# TriVCO_board_layout_FINAL_edited_10-22.net
KiCad netlist of a schematic drawn in EAGLE
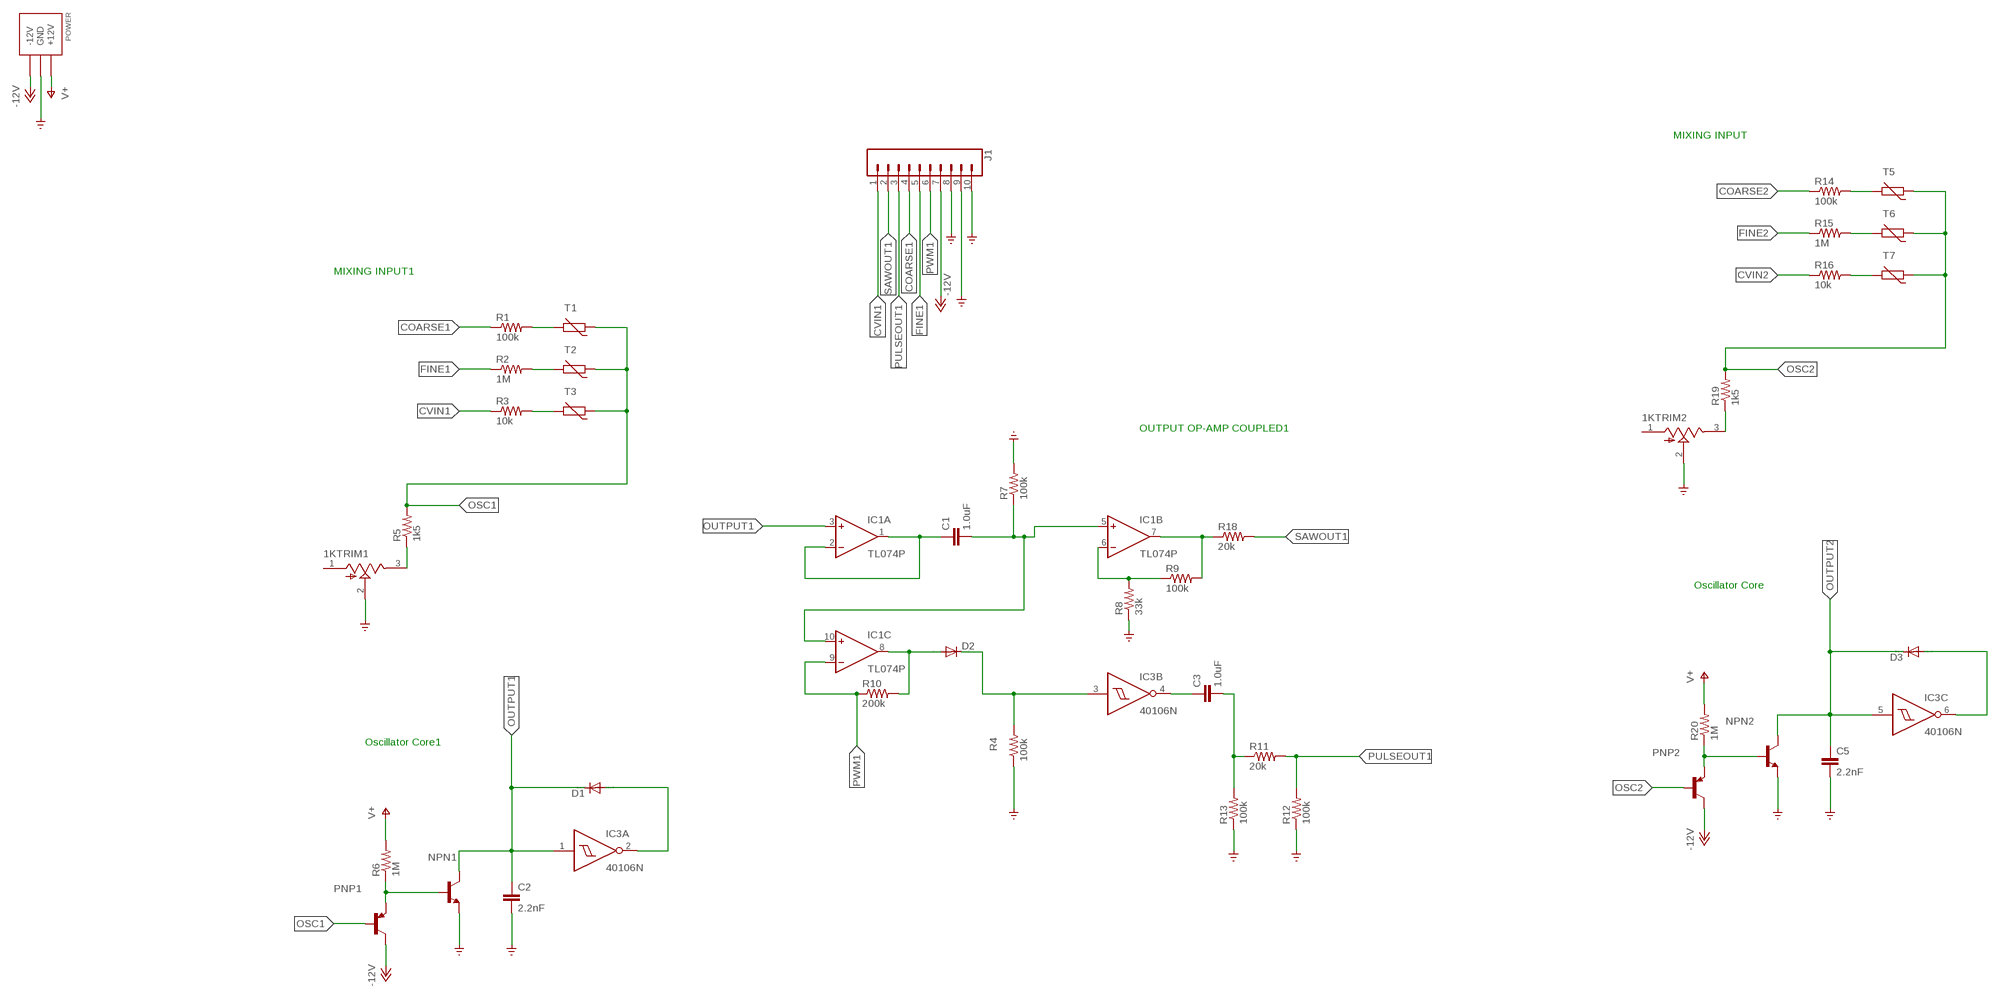
[diagram p0: schematic, sheet 1, part 1 of 2]
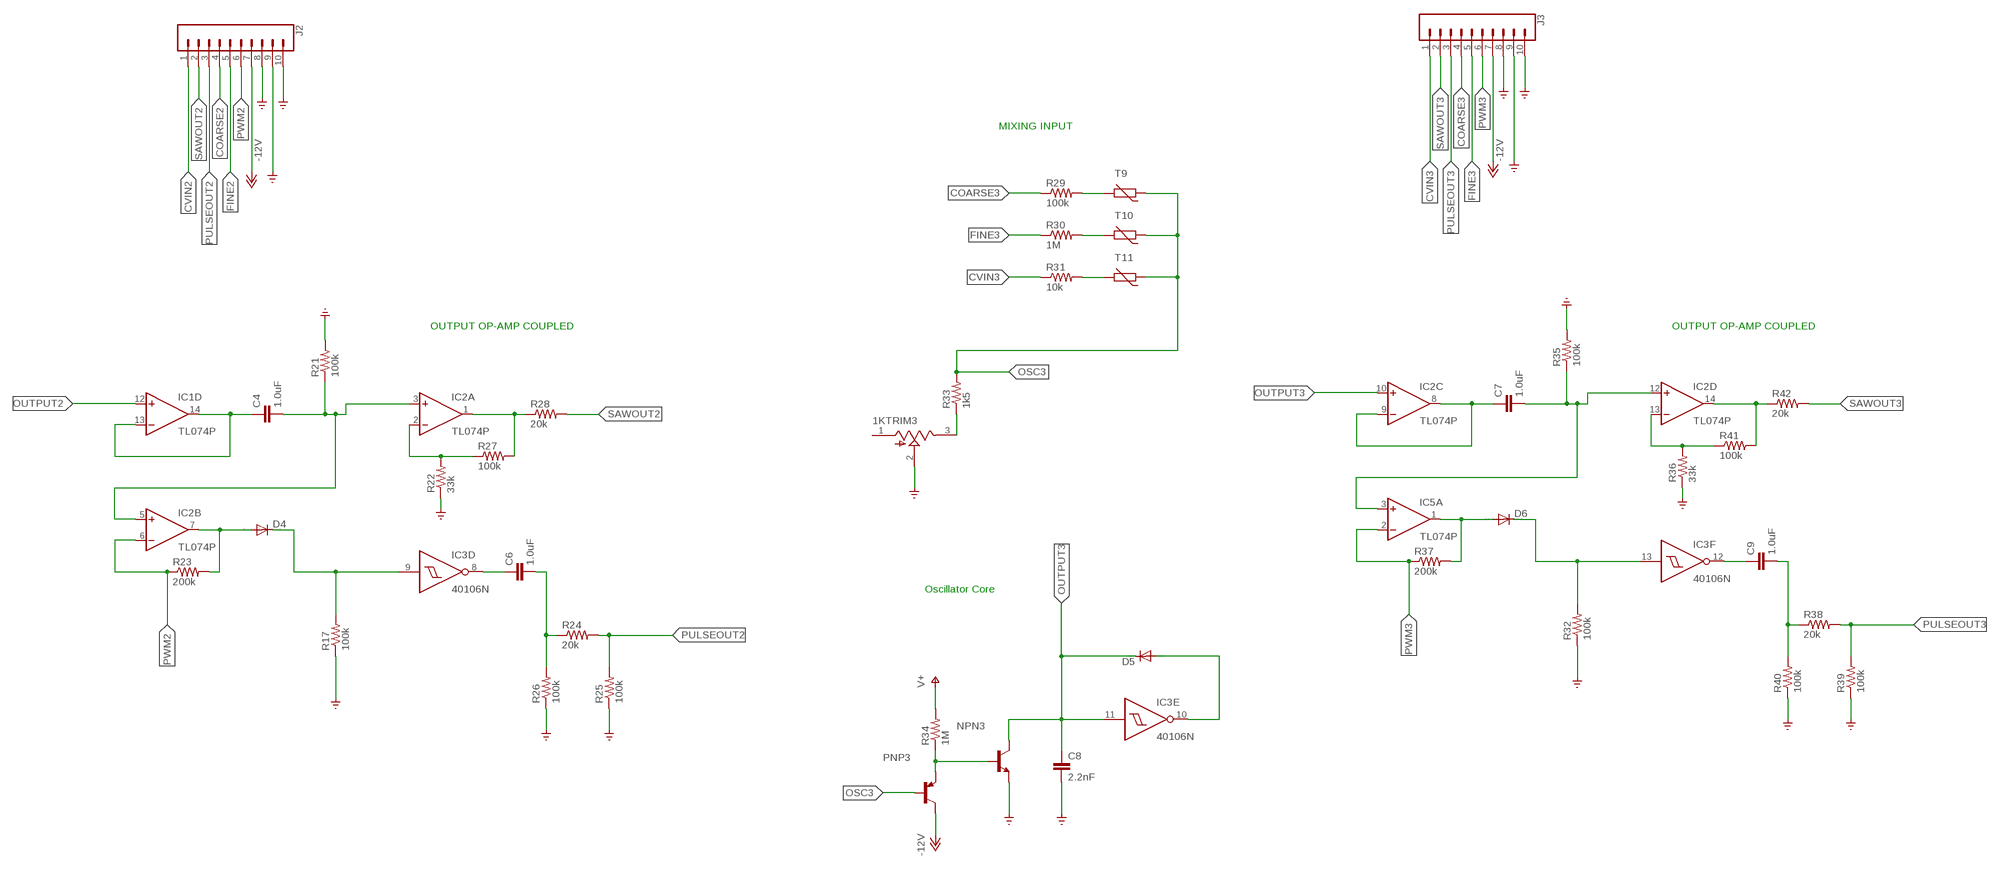
[diagram p1: schematic, sheet 1, part 2 of 2]

(export (version "E")
  (design (tool "Eeschema 10.0.6"))
  (components
    (comp (ref "1KTRIM1")
      (value "3362P-1-102LF")
      (footprint "eagle-import:TRIM_3362P-1-102LF")
      (fields (field (name "MF") "Bourns"))
      (libsource (lib "eagle-import") (part "3362P-1-102LF"))
    )
    (comp (ref "1KTRIM2")
      (value "3362P-1-102LF")
      (footprint "eagle-import:TRIM_3362P-1-102LF")
      (fields (field (name "MF") "Bourns"))
      (libsource (lib "eagle-import") (part "3362P-1-102LF"))
    )
    (comp (ref "1KTRIM3")
      (value "3362P-1-102LF")
      (footprint "eagle-import:TRIM_3362P-1-102LF")
      (fields (field (name "MF") "Bourns"))
      (libsource (lib "eagle-import") (part "3362P-1-102LF"))
    )
    (comp (ref "C1")
      (value "1.0uF")
      (footprint "eagle-import:0603")
      (libsource (lib "eagle-import") (part "1.0UF-0603-16V-10%"))
    )
    (comp (ref "C2")
      (value "2.2nF")
      (footprint "eagle-import:0603")
      (libsource (lib "eagle-import") (part "1.0UF-0603-16V-10%"))
    )
    (comp (ref "C3")
      (value "1.0uF")
      (footprint "eagle-import:0402")
      (libsource (lib "eagle-import") (part "1.0UF-0402-16V-10%"))
    )
    (comp (ref "C4")
      (value "1.0uF")
      (footprint "eagle-import:0603")
      (libsource (lib "eagle-import") (part "1.0UF-0603-16V-10%"))
    )
    (comp (ref "C5")
      (value "2.2nF")
      (footprint "eagle-import:0603")
      (libsource (lib "eagle-import") (part "1.0UF-0603-16V-10%"))
    )
    (comp (ref "C6")
      (value "1.0uF")
      (footprint "eagle-import:0402")
      (libsource (lib "eagle-import") (part "1.0UF-0402-16V-10%"))
    )
    (comp (ref "C7")
      (value "1.0uF")
      (footprint "eagle-import:0603")
      (libsource (lib "eagle-import") (part "1.0UF-0603-16V-10%"))
    )
    (comp (ref "C8")
      (value "2.2nF")
      (footprint "eagle-import:0603")
      (libsource (lib "eagle-import") (part "1.0UF-0603-16V-10%"))
    )
    (comp (ref "C9")
      (value "1.0uF")
      (footprint "eagle-import:0402")
      (libsource (lib "eagle-import") (part "1.0UF-0402-16V-10%"))
    )
    (comp (ref "D1")
      (value "1N4148DO35-7")
      (footprint "eagle-import:DO35-7")
      (libsource (lib "eagle-import") (part "1N4148DO35-7"))
    )
    (comp (ref "D2")
      (value "1N4148DO35-7")
      (footprint "eagle-import:DO35-7")
      (libsource (lib "eagle-import") (part "1N4148DO35-7"))
    )
    (comp (ref "D3")
      (value "1N4148DO35-7")
      (footprint "eagle-import:DO35-7")
      (libsource (lib "eagle-import") (part "1N4148DO35-7"))
    )
    (comp (ref "D4")
      (value "1N4148DO35-7")
      (footprint "eagle-import:DO35-7")
      (libsource (lib "eagle-import") (part "1N4148DO35-7"))
    )
    (comp (ref "D5")
      (value "1N4148DO35-7")
      (footprint "eagle-import:DO35-7")
      (libsource (lib "eagle-import") (part "1N4148DO35-7"))
    )
    (comp (ref "D6")
      (value "1N4148DO35-7")
      (footprint "eagle-import:DO35-7")
      (libsource (lib "eagle-import") (part "1N4148DO35-7"))
    )
    (comp (ref "IC1")
      (value "TL074P")
      (footprint "eagle-import:DIL14")
      (libsource (lib "eagle-import") (part "TL074P"))
    )
    (comp (ref "IC2")
      (value "TL074P")
      (footprint "eagle-import:DIL14")
      (libsource (lib "eagle-import") (part "TL074P"))
    )
    (comp (ref "IC3")
      (value "40106N")
      (footprint "eagle-import:DIL14")
      (libsource (lib "eagle-import") (part "40106N"))
    )
    (comp (ref "IC5")
      (value "TL074P")
      (footprint "eagle-import:DIL14")
      (libsource (lib "eagle-import") (part "TL074P"))
    )
    (comp (ref "J1")
      (value "CONN_10\"")
      (footprint "eagle-import:1X10")
      (libsource (lib "eagle-import") (part "CONN_10{dblquote}"))
    )
    (comp (ref "J2")
      (value "CONN_10\"")
      (footprint "eagle-import:1X10")
      (libsource (lib "eagle-import") (part "CONN_10{dblquote}"))
    )
    (comp (ref "J3")
      (value "CONN_10\"")
      (footprint "eagle-import:1X10")
      (libsource (lib "eagle-import") (part "CONN_10{dblquote}"))
    )
    (comp (ref "NPN1")
      (value "BC485-NPN-TO92-CBE")
      (footprint "eagle-import:TO92-CBE")
      (libsource (lib "eagle-import") (part "-NPN-TO92-CBEBC485"))
    )
    (comp (ref "NPN2")
      (value "BC485-NPN-TO92-CBE")
      (footprint "eagle-import:TO92-CBE")
      (libsource (lib "eagle-import") (part "-NPN-TO92-CBEBC485"))
    )
    (comp (ref "NPN3")
      (value "BC485-NPN-TO92-CBE")
      (footprint "eagle-import:TO92-CBE")
      (libsource (lib "eagle-import") (part "-NPN-TO92-CBEBC485"))
    )
    (comp (ref "PNP1")
      (value "BC450-PNP-TO92-EBC")
      (footprint "eagle-import:TO92-EBC")
      (libsource (lib "eagle-import") (part "-PNP-TO92-EBCBC450"))
    )
    (comp (ref "PNP2")
      (value "BC450-PNP-TO92-EBC")
      (footprint "eagle-import:TO92-EBC")
      (libsource (lib "eagle-import") (part "-PNP-TO92-EBCBC450"))
    )
    (comp (ref "PNP3")
      (value "BC450-PNP-TO92-EBC")
      (footprint "eagle-import:TO92-EBC")
      (libsource (lib "eagle-import") (part "-PNP-TO92-EBCBC450"))
    )
    (comp (ref "POWER")
      (value "POWER_SIMPLE10")
      (footprint "eagle-import:POWER_10")
      (libsource (lib "eagle-import") (part "POWER_SIMPLE10"))
    )
    (comp (ref "R1")
      (value "100k")
      (footprint "eagle-import:0207_10")
      (libsource (lib "eagle-import") (part "R-US_0207/10"))
    )
    (comp (ref "R2")
      (value "1M")
      (footprint "eagle-import:0207_10")
      (libsource (lib "eagle-import") (part "R-US_0207/10"))
    )
    (comp (ref "R3")
      (value "10k")
      (footprint "eagle-import:0207_10")
      (libsource (lib "eagle-import") (part "R-US_0207/10"))
    )
    (comp (ref "R4")
      (value "100k")
      (footprint "eagle-import:0207_10")
      (libsource (lib "eagle-import") (part "R-US_0207/10"))
    )
    (comp (ref "R5")
      (value "1k5")
      (footprint "eagle-import:0207_10")
      (libsource (lib "eagle-import") (part "R-US_0207/10"))
    )
    (comp (ref "R6")
      (value "1M")
      (footprint "eagle-import:0207_10")
      (libsource (lib "eagle-import") (part "R-US_0207/10"))
    )
    (comp (ref "R7")
      (value "100k")
      (footprint "eagle-import:0207_10")
      (libsource (lib "eagle-import") (part "R-US_0207/10"))
    )
    (comp (ref "R8")
      (value "33k")
      (footprint "eagle-import:0207_10")
      (libsource (lib "eagle-import") (part "R-US_0207/10"))
    )
    (comp (ref "R9")
      (value "100k")
      (footprint "eagle-import:0207_10")
      (libsource (lib "eagle-import") (part "R-US_0207/10"))
    )
    (comp (ref "R10")
      (value "200k")
      (footprint "eagle-import:0207_10")
      (libsource (lib "eagle-import") (part "R-US_0207/10"))
    )
    (comp (ref "R11")
      (value "20k")
      (footprint "eagle-import:0207_10")
      (libsource (lib "eagle-import") (part "R-US_0207/10"))
    )
    (comp (ref "R12")
      (value "100k")
      (footprint "eagle-import:0207_10")
      (libsource (lib "eagle-import") (part "R-US_0207/10"))
    )
    (comp (ref "R13")
      (value "100k")
      (footprint "eagle-import:0207_10")
      (libsource (lib "eagle-import") (part "R-US_0207/10"))
    )
    (comp (ref "R14")
      (value "100k")
      (footprint "eagle-import:0207_10")
      (libsource (lib "eagle-import") (part "R-US_0207/10"))
    )
    (comp (ref "R15")
      (value "1M")
      (footprint "eagle-import:0207_10")
      (libsource (lib "eagle-import") (part "R-US_0207/10"))
    )
    (comp (ref "R16")
      (value "10k")
      (footprint "eagle-import:0207_10")
      (libsource (lib "eagle-import") (part "R-US_0207/10"))
    )
    (comp (ref "R17")
      (value "100k")
      (footprint "eagle-import:0207_10")
      (libsource (lib "eagle-import") (part "R-US_0207/10"))
    )
    (comp (ref "R18")
      (value "20k")
      (footprint "eagle-import:0207_10")
      (libsource (lib "eagle-import") (part "R-US_0207/10"))
    )
    (comp (ref "R19")
      (value "1k5")
      (footprint "eagle-import:0207_10")
      (libsource (lib "eagle-import") (part "R-US_0207/10"))
    )
    (comp (ref "R20")
      (value "1M")
      (footprint "eagle-import:0207_10")
      (libsource (lib "eagle-import") (part "R-US_0207/10"))
    )
    (comp (ref "R21")
      (value "100k")
      (footprint "eagle-import:0207_10")
      (libsource (lib "eagle-import") (part "R-US_0207/10"))
    )
    (comp (ref "R22")
      (value "33k")
      (footprint "eagle-import:0207_10")
      (libsource (lib "eagle-import") (part "R-US_0207/10"))
    )
    (comp (ref "R23")
      (value "200k")
      (footprint "eagle-import:0207_10")
      (libsource (lib "eagle-import") (part "R-US_0207/10"))
    )
    (comp (ref "R24")
      (value "20k")
      (footprint "eagle-import:0207_10")
      (libsource (lib "eagle-import") (part "R-US_0207/10"))
    )
    (comp (ref "R25")
      (value "100k")
      (footprint "eagle-import:0207_10")
      (libsource (lib "eagle-import") (part "R-US_0207/10"))
    )
    (comp (ref "R26")
      (value "100k")
      (footprint "eagle-import:0207_10")
      (libsource (lib "eagle-import") (part "R-US_0207/10"))
    )
    (comp (ref "R27")
      (value "100k")
      (footprint "eagle-import:0207_10")
      (libsource (lib "eagle-import") (part "R-US_0207/10"))
    )
    (comp (ref "R28")
      (value "20k")
      (footprint "eagle-import:0207_10")
      (libsource (lib "eagle-import") (part "R-US_0207/10"))
    )
    (comp (ref "R29")
      (value "100k")
      (footprint "eagle-import:0207_10")
      (libsource (lib "eagle-import") (part "R-US_0207/10"))
    )
    (comp (ref "R30")
      (value "1M")
      (footprint "eagle-import:0207_10")
      (libsource (lib "eagle-import") (part "R-US_0207/10"))
    )
    (comp (ref "R31")
      (value "10k")
      (footprint "eagle-import:0207_10")
      (libsource (lib "eagle-import") (part "R-US_0207/10"))
    )
    (comp (ref "R32")
      (value "100k")
      (footprint "eagle-import:0207_10")
      (libsource (lib "eagle-import") (part "R-US_0207/10"))
    )
    (comp (ref "R33")
      (value "1k5")
      (footprint "eagle-import:0207_10")
      (libsource (lib "eagle-import") (part "R-US_0207/10"))
    )
    (comp (ref "R34")
      (value "1M")
      (footprint "eagle-import:0207_10")
      (libsource (lib "eagle-import") (part "R-US_0207/10"))
    )
    (comp (ref "R35")
      (value "100k")
      (footprint "eagle-import:0207_10")
      (libsource (lib "eagle-import") (part "R-US_0207/10"))
    )
    (comp (ref "R36")
      (value "33k")
      (footprint "eagle-import:0207_10")
      (libsource (lib "eagle-import") (part "R-US_0207/10"))
    )
    (comp (ref "R37")
      (value "200k")
      (footprint "eagle-import:0207_10")
      (libsource (lib "eagle-import") (part "R-US_0207/10"))
    )
    (comp (ref "R38")
      (value "20k")
      (footprint "eagle-import:0207_10")
      (libsource (lib "eagle-import") (part "R-US_0207/10"))
    )
    (comp (ref "R39")
      (value "100k")
      (footprint "eagle-import:0207_10")
      (libsource (lib "eagle-import") (part "R-US_0207/10"))
    )
    (comp (ref "R40")
      (value "100k")
      (footprint "eagle-import:0207_10")
      (libsource (lib "eagle-import") (part "R-US_0207/10"))
    )
    (comp (ref "R41")
      (value "100k")
      (footprint "eagle-import:0207_10")
      (libsource (lib "eagle-import") (part "R-US_0207/10"))
    )
    (comp (ref "R42")
      (value "20k")
      (footprint "eagle-import:0207_10")
      (libsource (lib "eagle-import") (part "R-US_0207/10"))
    )
    (comp (ref "T1")
      (value "THERMISTOR-5")
      (footprint "eagle-import:R-5")
      (libsource (lib "eagle-import") (part "THERMISTOR-5"))
    )
    (comp (ref "T2")
      (value "THERMISTOR-5")
      (footprint "eagle-import:R-5")
      (libsource (lib "eagle-import") (part "THERMISTOR-5"))
    )
    (comp (ref "T3")
      (value "THERMISTOR-5")
      (footprint "eagle-import:R-5")
      (libsource (lib "eagle-import") (part "THERMISTOR-5"))
    )
    (comp (ref "T5")
      (value "THERMISTOR-5")
      (footprint "eagle-import:R-5")
      (libsource (lib "eagle-import") (part "THERMISTOR-5"))
    )
    (comp (ref "T6")
      (value "THERMISTOR-5")
      (footprint "eagle-import:R-5")
      (libsource (lib "eagle-import") (part "THERMISTOR-5"))
    )
    (comp (ref "T7")
      (value "THERMISTOR-5")
      (footprint "eagle-import:R-5")
      (libsource (lib "eagle-import") (part "THERMISTOR-5"))
    )
    (comp (ref "T9")
      (value "THERMISTOR-5")
      (footprint "eagle-import:R-5")
      (libsource (lib "eagle-import") (part "THERMISTOR-5"))
    )
    (comp (ref "T10")
      (value "THERMISTOR-5")
      (footprint "eagle-import:R-5")
      (libsource (lib "eagle-import") (part "THERMISTOR-5"))
    )
    (comp (ref "T11")
      (value "THERMISTOR-5")
      (footprint "eagle-import:R-5")
      (libsource (lib "eagle-import") (part "THERMISTOR-5"))
    )
  )
  (nets
    (net (code "1") (name "-12V") (class "Default")
      (node (ref "J1") (pin "7") (pinfunction "7_7") (pintype "passive"))
      (node (ref "J2") (pin "7") (pinfunction "7_7") (pintype "passive"))
      (node (ref "J3") (pin "7") (pinfunction "7_7") (pintype "passive"))
      (node (ref "PNP1") (pin "C") (pinfunction "C_C") (pintype "passive"))
      (node (ref "PNP2") (pin "C") (pinfunction "C_C") (pintype "passive"))
      (node (ref "PNP3") (pin "C") (pinfunction "C_C") (pintype "passive"))
      (node (ref "POWER") (pin "1") (pinfunction "-12V_1") (pintype "bidirectional"))
      (node (ref "POWER") (pin "2") (pinfunction "-12V_2") (pintype "bidirectional"))
    )
    (net (code "2") (name "COARSE1") (class "Default")
      (node (ref "J1") (pin "4") (pinfunction "4_4") (pintype "passive"))
      (node (ref "R1") (pin "1") (pinfunction "1_1") (pintype "passive"))
    )
    (net (code "3") (name "COARSE2") (class "Default")
      (node (ref "J2") (pin "4") (pinfunction "4_4") (pintype "passive"))
      (node (ref "R14") (pin "1") (pinfunction "1_1") (pintype "passive"))
    )
    (net (code "4") (name "COARSE3") (class "Default")
      (node (ref "J3") (pin "4") (pinfunction "4_4") (pintype "passive"))
      (node (ref "R29") (pin "1") (pinfunction "1_1") (pintype "passive"))
    )
    (net (code "5") (name "CVIN1") (class "Default")
      (node (ref "J1") (pin "1") (pinfunction "1_1") (pintype "passive"))
      (node (ref "R3") (pin "1") (pinfunction "1_1") (pintype "passive"))
    )
    (net (code "6") (name "CVIN2") (class "Default")
      (node (ref "J2") (pin "1") (pinfunction "1_1") (pintype "passive"))
      (node (ref "R16") (pin "1") (pinfunction "1_1") (pintype "passive"))
    )
    (net (code "7") (name "CVIN3") (class "Default")
      (node (ref "J3") (pin "1") (pinfunction "1_1") (pintype "passive"))
      (node (ref "R31") (pin "1") (pinfunction "1_1") (pintype "passive"))
    )
    (net (code "8") (name "FINE1") (class "Default")
      (node (ref "J1") (pin "5") (pinfunction "5_5") (pintype "passive"))
      (node (ref "R2") (pin "1") (pinfunction "1_1") (pintype "passive"))
    )
    (net (code "9") (name "FINE2") (class "Default")
      (node (ref "J2") (pin "5") (pinfunction "5_5") (pintype "passive"))
      (node (ref "R15") (pin "1") (pinfunction "1_1") (pintype "passive"))
    )
    (net (code "10") (name "FINE3") (class "Default")
      (node (ref "J3") (pin "5") (pinfunction "5_5") (pintype "passive"))
      (node (ref "R30") (pin "1") (pinfunction "1_1") (pintype "passive"))
    )
    (net (code "11") (name "Net-(1KTRIM1-CW)") (class "Default")
      (node (ref "1KTRIM1") (pin "3") (pinfunction "CW_3") (pintype "passive"))
      (node (ref "R5") (pin "1") (pinfunction "1_1") (pintype "passive"))
    )
    (net (code "12") (name "Net-(1KTRIM2-CW)") (class "Default")
      (node (ref "1KTRIM2") (pin "3") (pinfunction "CW_3") (pintype "passive"))
      (node (ref "R19") (pin "1") (pinfunction "1_1") (pintype "passive"))
    )
    (net (code "13") (name "Net-(1KTRIM3-CW)") (class "Default")
      (node (ref "1KTRIM3") (pin "3") (pinfunction "CW_3") (pintype "passive"))
      (node (ref "R33") (pin "1") (pinfunction "1_1") (pintype "passive"))
    )
    (net (code "14") (name "Net-(C3-Pad2)") (class "Default")
      (node (ref "C3") (pin "2") (pinfunction "2_2") (pintype "passive"))
      (node (ref "R11") (pin "1") (pinfunction "1_1") (pintype "passive"))
      (node (ref "R13") (pin "2") (pinfunction "2_2") (pintype "passive"))
    )
    (net (code "15") (name "Net-(C6-Pad2)") (class "Default")
      (node (ref "C6") (pin "2") (pinfunction "2_2") (pintype "passive"))
      (node (ref "R24") (pin "1") (pinfunction "1_1") (pintype "passive"))
      (node (ref "R26") (pin "2") (pinfunction "2_2") (pintype "passive"))
    )
    (net (code "16") (name "Net-(C9-Pad2)") (class "Default")
      (node (ref "C9") (pin "2") (pinfunction "2_2") (pintype "passive"))
      (node (ref "R38") (pin "1") (pinfunction "1_1") (pintype "passive"))
      (node (ref "R40") (pin "2") (pinfunction "2_2") (pintype "passive"))
    )
    (net (code "17") (name "Net-(IC1A--IN)") (class "Default")
      (node (ref "C1") (pin "1") (pinfunction "1_1") (pintype "passive"))
      (node (ref "IC1") (pin "1") (pinfunction "OUT_1") (pintype "output"))
      (node (ref "IC1") (pin "2") (pinfunction "-IN_2") (pintype "input"))
    )
    (net (code "18") (name "Net-(IC1B-+IN)") (class "Default")
      (node (ref "C1") (pin "2") (pinfunction "2_2") (pintype "passive"))
      (node (ref "IC1") (pin "10") (pinfunction "+IN_10") (pintype "input"))
      (node (ref "IC1") (pin "5") (pinfunction "+IN_5") (pintype "input"))
      (node (ref "R7") (pin "1") (pinfunction "1_1") (pintype "passive"))
    )
    (net (code "19") (name "Net-(IC1B--IN)") (class "Default")
      (node (ref "IC1") (pin "6") (pinfunction "-IN_6") (pintype "input"))
      (node (ref "R8") (pin "2") (pinfunction "2_2") (pintype "passive"))
      (node (ref "R9") (pin "1") (pinfunction "1_1") (pintype "passive"))
    )
    (net (code "20") (name "Net-(IC1B-OUT)") (class "Default")
      (node (ref "IC1") (pin "7") (pinfunction "OUT_7") (pintype "output"))
      (node (ref "R18") (pin "1") (pinfunction "1_1") (pintype "passive"))
      (node (ref "R9") (pin "2") (pinfunction "2_2") (pintype "passive"))
    )
    (net (code "21") (name "Net-(IC1C-OUT)") (class "Default")
      (node (ref "D2") (pin "A") (pinfunction "A_A") (pintype "passive"))
      (node (ref "IC1") (pin "8") (pinfunction "OUT_8") (pintype "output"))
      (node (ref "R10") (pin "2") (pinfunction "2_2") (pintype "passive"))
    )
    (net (code "22") (name "Net-(IC1D--IN)") (class "Default")
      (node (ref "C4") (pin "1") (pinfunction "1_1") (pintype "passive"))
      (node (ref "IC1") (pin "13") (pinfunction "-IN_13") (pintype "input"))
      (node (ref "IC1") (pin "14") (pinfunction "OUT_14") (pintype "output"))
    )
    (net (code "23") (name "Net-(IC2A-+IN)") (class "Default")
      (node (ref "C4") (pin "2") (pinfunction "2_2") (pintype "passive"))
      (node (ref "IC2") (pin "3") (pinfunction "+IN_3") (pintype "input"))
      (node (ref "IC2") (pin "5") (pinfunction "+IN_5") (pintype "input"))
      (node (ref "R21") (pin "1") (pinfunction "1_1") (pintype "passive"))
    )
    (net (code "24") (name "Net-(IC2A--IN)") (class "Default")
      (node (ref "IC2") (pin "2") (pinfunction "-IN_2") (pintype "input"))
      (node (ref "R22") (pin "2") (pinfunction "2_2") (pintype "passive"))
      (node (ref "R27") (pin "1") (pinfunction "1_1") (pintype "passive"))
    )
    (net (code "25") (name "Net-(IC2A-OUT)") (class "Default")
      (node (ref "IC2") (pin "1") (pinfunction "OUT_1") (pintype "output"))
      (node (ref "R27") (pin "2") (pinfunction "2_2") (pintype "passive"))
      (node (ref "R28") (pin "1") (pinfunction "1_1") (pintype "passive"))
    )
    (net (code "26") (name "Net-(IC2B-OUT)") (class "Default")
      (node (ref "D4") (pin "A") (pinfunction "A_A") (pintype "passive"))
      (node (ref "IC2") (pin "7") (pinfunction "OUT_7") (pintype "output"))
      (node (ref "R23") (pin "2") (pinfunction "2_2") (pintype "passive"))
    )
    (net (code "27") (name "Net-(IC2C--IN)") (class "Default")
      (node (ref "C7") (pin "1") (pinfunction "1_1") (pintype "passive"))
      (node (ref "IC2") (pin "8") (pinfunction "OUT_8") (pintype "output"))
      (node (ref "IC2") (pin "9") (pinfunction "-IN_9") (pintype "input"))
    )
    (net (code "28") (name "Net-(IC2D-+IN)") (class "Default")
      (node (ref "C7") (pin "2") (pinfunction "2_2") (pintype "passive"))
      (node (ref "IC2") (pin "12") (pinfunction "+IN_12") (pintype "input"))
      (node (ref "IC5") (pin "3") (pinfunction "+IN_3") (pintype "input"))
      (node (ref "R35") (pin "1") (pinfunction "1_1") (pintype "passive"))
    )
    (net (code "29") (name "Net-(IC2D--IN)") (class "Default")
      (node (ref "IC2") (pin "13") (pinfunction "-IN_13") (pintype "input"))
      (node (ref "R36") (pin "2") (pinfunction "2_2") (pintype "passive"))
      (node (ref "R41") (pin "1") (pinfunction "1_1") (pintype "passive"))
    )
    (net (code "30") (name "Net-(IC2D-OUT)") (class "Default")
      (node (ref "IC2") (pin "14") (pinfunction "OUT_14") (pintype "output"))
      (node (ref "R41") (pin "2") (pinfunction "2_2") (pintype "passive"))
      (node (ref "R42") (pin "1") (pinfunction "1_1") (pintype "passive"))
    )
    (net (code "31") (name "Net-(IC3A-O)") (class "Default")
      (node (ref "D1") (pin "A") (pinfunction "A_A") (pintype "passive"))
      (node (ref "IC3") (pin "2") (pinfunction "O_2") (pintype "output"))
    )
    (net (code "32") (name "Net-(IC3B-I)") (class "Default")
      (node (ref "D2") (pin "C") (pinfunction "C_C") (pintype "passive"))
      (node (ref "IC3") (pin "3") (pinfunction "I_3") (pintype "input"))
      (node (ref "R4") (pin "2") (pinfunction "2_2") (pintype "passive"))
    )
    (net (code "33") (name "Net-(IC3B-O)") (class "Default")
      (node (ref "C3") (pin "1") (pinfunction "1_1") (pintype "passive"))
      (node (ref "IC3") (pin "4") (pinfunction "O_4") (pintype "output"))
    )
    (net (code "34") (name "Net-(IC3C-O)") (class "Default")
      (node (ref "D3") (pin "A") (pinfunction "A_A") (pintype "passive"))
      (node (ref "IC3") (pin "6") (pinfunction "O_6") (pintype "output"))
    )
    (net (code "35") (name "Net-(IC3D-I)") (class "Default")
      (node (ref "D4") (pin "C") (pinfunction "C_C") (pintype "passive"))
      (node (ref "IC3") (pin "9") (pinfunction "I_9") (pintype "input"))
      (node (ref "R17") (pin "2") (pinfunction "2_2") (pintype "passive"))
    )
    (net (code "36") (name "Net-(IC3D-O)") (class "Default")
      (node (ref "C6") (pin "1") (pinfunction "1_1") (pintype "passive"))
      (node (ref "IC3") (pin "8") (pinfunction "O_8") (pintype "output"))
    )
    (net (code "37") (name "Net-(IC3E-O)") (class "Default")
      (node (ref "D5") (pin "A") (pinfunction "A_A") (pintype "passive"))
      (node (ref "IC3") (pin "10") (pinfunction "O_10") (pintype "output"))
    )
    (net (code "38") (name "Net-(IC3F-I)") (class "Default")
      (node (ref "D6") (pin "C") (pinfunction "C_C") (pintype "passive"))
      (node (ref "IC3") (pin "13") (pinfunction "I_13") (pintype "input"))
      (node (ref "R32") (pin "2") (pinfunction "2_2") (pintype "passive"))
    )
    (net (code "39") (name "Net-(IC3F-O)") (class "Default")
      (node (ref "C9") (pin "1") (pinfunction "1_1") (pintype "passive"))
      (node (ref "IC3") (pin "12") (pinfunction "O_12") (pintype "output"))
    )
    (net (code "40") (name "Net-(IC5A-OUT)") (class "Default")
      (node (ref "D6") (pin "A") (pinfunction "A_A") (pintype "passive"))
      (node (ref "IC5") (pin "1") (pinfunction "OUT_1") (pintype "output"))
      (node (ref "R37") (pin "2") (pinfunction "2_2") (pintype "passive"))
    )
    (net (code "41") (name "Net-(NPN1-PadB)") (class "Default")
      (node (ref "NPN1") (pin "B") (pinfunction "B_B") (pintype "passive"))
      (node (ref "PNP1") (pin "E") (pinfunction "E_E") (pintype "passive"))
      (node (ref "R6") (pin "1") (pinfunction "1_1") (pintype "passive"))
    )
    (net (code "42") (name "Net-(NPN2-PadB)") (class "Default")
      (node (ref "NPN2") (pin "B") (pinfunction "B_B") (pintype "passive"))
      (node (ref "PNP2") (pin "E") (pinfunction "E_E") (pintype "passive"))
      (node (ref "R20") (pin "1") (pinfunction "1_1") (pintype "passive"))
    )
    (net (code "43") (name "Net-(NPN3-PadB)") (class "Default")
      (node (ref "NPN3") (pin "B") (pinfunction "B_B") (pintype "passive"))
      (node (ref "PNP3") (pin "E") (pinfunction "E_E") (pintype "passive"))
      (node (ref "R34") (pin "1") (pinfunction "1_1") (pintype "passive"))
    )
    (net (code "44") (name "Net-(R1-Pad2)") (class "Default")
      (node (ref "R1") (pin "2") (pinfunction "2_2") (pintype "passive"))
      (node (ref "T1") (pin "2") (pinfunction "2_2") (pintype "passive"))
    )
    (net (code "45") (name "Net-(R2-Pad2)") (class "Default")
      (node (ref "R2") (pin "2") (pinfunction "2_2") (pintype "passive"))
      (node (ref "T2") (pin "2") (pinfunction "2_2") (pintype "passive"))
    )
    (net (code "46") (name "Net-(R3-Pad2)") (class "Default")
      (node (ref "R3") (pin "2") (pinfunction "2_2") (pintype "passive"))
      (node (ref "T3") (pin "2") (pinfunction "2_2") (pintype "passive"))
    )
    (net (code "47") (name "Net-(R14-Pad2)") (class "Default")
      (node (ref "R14") (pin "2") (pinfunction "2_2") (pintype "passive"))
      (node (ref "T5") (pin "2") (pinfunction "2_2") (pintype "passive"))
    )
    (net (code "48") (name "Net-(R15-Pad2)") (class "Default")
      (node (ref "R15") (pin "2") (pinfunction "2_2") (pintype "passive"))
      (node (ref "T6") (pin "2") (pinfunction "2_2") (pintype "passive"))
    )
    (net (code "49") (name "Net-(R16-Pad2)") (class "Default")
      (node (ref "R16") (pin "2") (pinfunction "2_2") (pintype "passive"))
      (node (ref "T7") (pin "2") (pinfunction "2_2") (pintype "passive"))
    )
    (net (code "50") (name "Net-(R29-Pad2)") (class "Default")
      (node (ref "R29") (pin "2") (pinfunction "2_2") (pintype "passive"))
      (node (ref "T9") (pin "2") (pinfunction "2_2") (pintype "passive"))
    )
    (net (code "51") (name "Net-(R30-Pad2)") (class "Default")
      (node (ref "R30") (pin "2") (pinfunction "2_2") (pintype "passive"))
      (node (ref "T10") (pin "2") (pinfunction "2_2") (pintype "passive"))
    )
    (net (code "52") (name "Net-(R31-Pad2)") (class "Default")
      (node (ref "R31") (pin "2") (pinfunction "2_2") (pintype "passive"))
      (node (ref "T11") (pin "2") (pinfunction "2_2") (pintype "passive"))
    )
    (net (code "53") (name "OSC1") (class "Default")
      (node (ref "PNP1") (pin "B") (pinfunction "B_B") (pintype "passive"))
      (node (ref "R5") (pin "2") (pinfunction "2_2") (pintype "passive"))
      (node (ref "T1") (pin "1") (pinfunction "1_1") (pintype "passive"))
      (node (ref "T2") (pin "1") (pinfunction "1_1") (pintype "passive"))
      (node (ref "T3") (pin "1") (pinfunction "1_1") (pintype "passive"))
    )
    (net (code "54") (name "OSC2") (class "Default")
      (node (ref "PNP2") (pin "B") (pinfunction "B_B") (pintype "passive"))
      (node (ref "R19") (pin "2") (pinfunction "2_2") (pintype "passive"))
      (node (ref "T5") (pin "1") (pinfunction "1_1") (pintype "passive"))
      (node (ref "T6") (pin "1") (pinfunction "1_1") (pintype "passive"))
      (node (ref "T7") (pin "1") (pinfunction "1_1") (pintype "passive"))
    )
    (net (code "55") (name "OSC3") (class "Default")
      (node (ref "PNP3") (pin "B") (pinfunction "B_B") (pintype "passive"))
      (node (ref "R33") (pin "2") (pinfunction "2_2") (pintype "passive"))
      (node (ref "T10") (pin "1") (pinfunction "1_1") (pintype "passive"))
      (node (ref "T11") (pin "1") (pinfunction "1_1") (pintype "passive"))
      (node (ref "T9") (pin "1") (pinfunction "1_1") (pintype "passive"))
    )
    (net (code "56") (name "OUTPUT1") (class "Default")
      (node (ref "C2") (pin "1") (pinfunction "1_1") (pintype "passive"))
      (node (ref "D1") (pin "C") (pinfunction "C_C") (pintype "passive"))
      (node (ref "IC1") (pin "3") (pinfunction "+IN_3") (pintype "input"))
      (node (ref "IC3") (pin "1") (pinfunction "I_1") (pintype "input"))
      (node (ref "NPN1") (pin "C") (pinfunction "C_C") (pintype "passive"))
    )
    (net (code "57") (name "OUTPUT2") (class "Default")
      (node (ref "C5") (pin "1") (pinfunction "1_1") (pintype "passive"))
      (node (ref "D3") (pin "C") (pinfunction "C_C") (pintype "passive"))
      (node (ref "IC1") (pin "12") (pinfunction "+IN_12") (pintype "input"))
      (node (ref "IC3") (pin "5") (pinfunction "I_5") (pintype "input"))
      (node (ref "NPN2") (pin "C") (pinfunction "C_C") (pintype "passive"))
    )
    (net (code "58") (name "OUTPUT3") (class "Default")
      (node (ref "C8") (pin "1") (pinfunction "1_1") (pintype "passive"))
      (node (ref "D5") (pin "C") (pinfunction "C_C") (pintype "passive"))
      (node (ref "IC2") (pin "10") (pinfunction "+IN_10") (pintype "input"))
      (node (ref "IC3") (pin "11") (pinfunction "I_11") (pintype "input"))
      (node (ref "NPN3") (pin "C") (pinfunction "C_C") (pintype "passive"))
    )
    (net (code "59") (name "PULSEOUT1") (class "Default")
      (node (ref "J1") (pin "3") (pinfunction "3_3") (pintype "passive"))
      (node (ref "R11") (pin "2") (pinfunction "2_2") (pintype "passive"))
      (node (ref "R12") (pin "2") (pinfunction "2_2") (pintype "passive"))
    )
    (net (code "60") (name "PULSEOUT2") (class "Default")
      (node (ref "J2") (pin "3") (pinfunction "3_3") (pintype "passive"))
      (node (ref "R24") (pin "2") (pinfunction "2_2") (pintype "passive"))
      (node (ref "R25") (pin "2") (pinfunction "2_2") (pintype "passive"))
    )
    (net (code "61") (name "PULSEOUT3") (class "Default")
      (node (ref "J3") (pin "3") (pinfunction "3_3") (pintype "passive"))
      (node (ref "R38") (pin "2") (pinfunction "2_2") (pintype "passive"))
      (node (ref "R39") (pin "2") (pinfunction "2_2") (pintype "passive"))
    )
    (net (code "62") (name "PWM1") (class "Default")
      (node (ref "IC1") (pin "9") (pinfunction "-IN_9") (pintype "input"))
      (node (ref "J1") (pin "6") (pinfunction "6_6") (pintype "passive"))
      (node (ref "R10") (pin "1") (pinfunction "1_1") (pintype "passive"))
    )
    (net (code "63") (name "PWM2") (class "Default")
      (node (ref "IC2") (pin "6") (pinfunction "-IN_6") (pintype "input"))
      (node (ref "J2") (pin "6") (pinfunction "6_6") (pintype "passive"))
      (node (ref "R23") (pin "1") (pinfunction "1_1") (pintype "passive"))
    )
    (net (code "64") (name "PWM3") (class "Default")
      (node (ref "IC5") (pin "2") (pinfunction "-IN_2") (pintype "input"))
      (node (ref "J3") (pin "6") (pinfunction "6_6") (pintype "passive"))
      (node (ref "R37") (pin "1") (pinfunction "1_1") (pintype "passive"))
    )
    (net (code "65") (name "SAWOUT1") (class "Default")
      (node (ref "J1") (pin "2") (pinfunction "2_2") (pintype "passive"))
      (node (ref "R18") (pin "2") (pinfunction "2_2") (pintype "passive"))
    )
    (net (code "66") (name "SAWOUT2") (class "Default")
      (node (ref "J2") (pin "2") (pinfunction "2_2") (pintype "passive"))
      (node (ref "R28") (pin "2") (pinfunction "2_2") (pintype "passive"))
    )
    (net (code "67") (name "SAWOUT3") (class "Default")
      (node (ref "J3") (pin "2") (pinfunction "2_2") (pintype "passive"))
      (node (ref "R42") (pin "2") (pinfunction "2_2") (pintype "passive"))
    )
    (net (code "68") (name "SUPPLY0_GND_") (class "Default")
      (node (ref "1KTRIM1") (pin "2") (pinfunction "WIPER_2") (pintype "passive"))
      (node (ref "1KTRIM2") (pin "2") (pinfunction "WIPER_2") (pintype "passive"))
      (node (ref "1KTRIM3") (pin "2") (pinfunction "WIPER_2") (pintype "passive"))
      (node (ref "C2") (pin "2") (pinfunction "2_2") (pintype "passive"))
      (node (ref "C5") (pin "2") (pinfunction "2_2") (pintype "passive"))
      (node (ref "C8") (pin "2") (pinfunction "2_2") (pintype "passive"))
      (node (ref "J1") (pin "10") (pinfunction "10_10") (pintype "passive"))
      (node (ref "J1") (pin "8") (pinfunction "8_8") (pintype "passive"))
      (node (ref "J1") (pin "9") (pinfunction "9_9") (pintype "passive"))
      (node (ref "J2") (pin "10") (pinfunction "10_10") (pintype "passive"))
      (node (ref "J2") (pin "8") (pinfunction "8_8") (pintype "passive"))
      (node (ref "J2") (pin "9") (pinfunction "9_9") (pintype "passive"))
      (node (ref "J3") (pin "10") (pinfunction "10_10") (pintype "passive"))
      (node (ref "J3") (pin "8") (pinfunction "8_8") (pintype "passive"))
      (node (ref "J3") (pin "9") (pinfunction "9_9") (pintype "passive"))
      (node (ref "NPN1") (pin "E") (pinfunction "E_E") (pintype "passive"))
      (node (ref "NPN2") (pin "E") (pinfunction "E_E") (pintype "passive"))
      (node (ref "NPN3") (pin "E") (pinfunction "E_E") (pintype "passive"))
      (node (ref "POWER") (pin "3") (pinfunction "GND_3") (pintype "bidirectional"))
      (node (ref "POWER") (pin "4") (pinfunction "GND_4") (pintype "bidirectional"))
      (node (ref "POWER") (pin "5") (pinfunction "GND_5") (pintype "bidirectional"))
      (node (ref "POWER") (pin "6") (pinfunction "GND_6") (pintype "bidirectional"))
      (node (ref "POWER") (pin "7") (pinfunction "GND_7") (pintype "bidirectional"))
      (node (ref "POWER") (pin "8") (pinfunction "GND_8") (pintype "bidirectional"))
      (node (ref "R12") (pin "1") (pinfunction "1_1") (pintype "passive"))
      (node (ref "R13") (pin "1") (pinfunction "1_1") (pintype "passive"))
      (node (ref "R17") (pin "1") (pinfunction "1_1") (pintype "passive"))
      (node (ref "R21") (pin "2") (pinfunction "2_2") (pintype "passive"))
      (node (ref "R22") (pin "1") (pinfunction "1_1") (pintype "passive"))
      (node (ref "R25") (pin "1") (pinfunction "1_1") (pintype "passive"))
      (node (ref "R26") (pin "1") (pinfunction "1_1") (pintype "passive"))
      (node (ref "R32") (pin "1") (pinfunction "1_1") (pintype "passive"))
      (node (ref "R35") (pin "2") (pinfunction "2_2") (pintype "passive"))
      (node (ref "R36") (pin "1") (pinfunction "1_1") (pintype "passive"))
      (node (ref "R39") (pin "1") (pinfunction "1_1") (pintype "passive"))
      (node (ref "R4") (pin "1") (pinfunction "1_1") (pintype "passive"))
      (node (ref "R40") (pin "1") (pinfunction "1_1") (pintype "passive"))
      (node (ref "R7") (pin "2") (pinfunction "2_2") (pintype "passive"))
      (node (ref "R8") (pin "1") (pinfunction "1_1") (pintype "passive"))
    )
    (net (code "69") (name "V+") (class "Default")
      (node (ref "POWER") (pin "10") (pinfunction "+12V_10") (pintype "bidirectional"))
      (node (ref "POWER") (pin "9") (pinfunction "+12V_9") (pintype "bidirectional"))
      (node (ref "R20") (pin "2") (pinfunction "2_2") (pintype "passive"))
      (node (ref "R34") (pin "2") (pinfunction "2_2") (pintype "passive"))
      (node (ref "R6") (pin "2") (pinfunction "2_2") (pintype "passive"))
    )
    (net (code "70") (name "unconnected-(1KTRIM1-CCW-Pad1)") (class "Default")
      (node (ref "1KTRIM1") (pin "1") (pinfunction "CCW_1") (pintype "passive"))
    )
    (net (code "71") (name "unconnected-(1KTRIM2-CCW-Pad1)") (class "Default")
      (node (ref "1KTRIM2") (pin "1") (pinfunction "CCW_1") (pintype "passive"))
    )
    (net (code "72") (name "unconnected-(1KTRIM3-CCW-Pad1)") (class "Default")
      (node (ref "1KTRIM3") (pin "1") (pinfunction "CCW_1") (pintype "passive"))
    )
  )
)
